# CAN_Node.net
KiCad netlist of a schematic drawn in Altium Designer
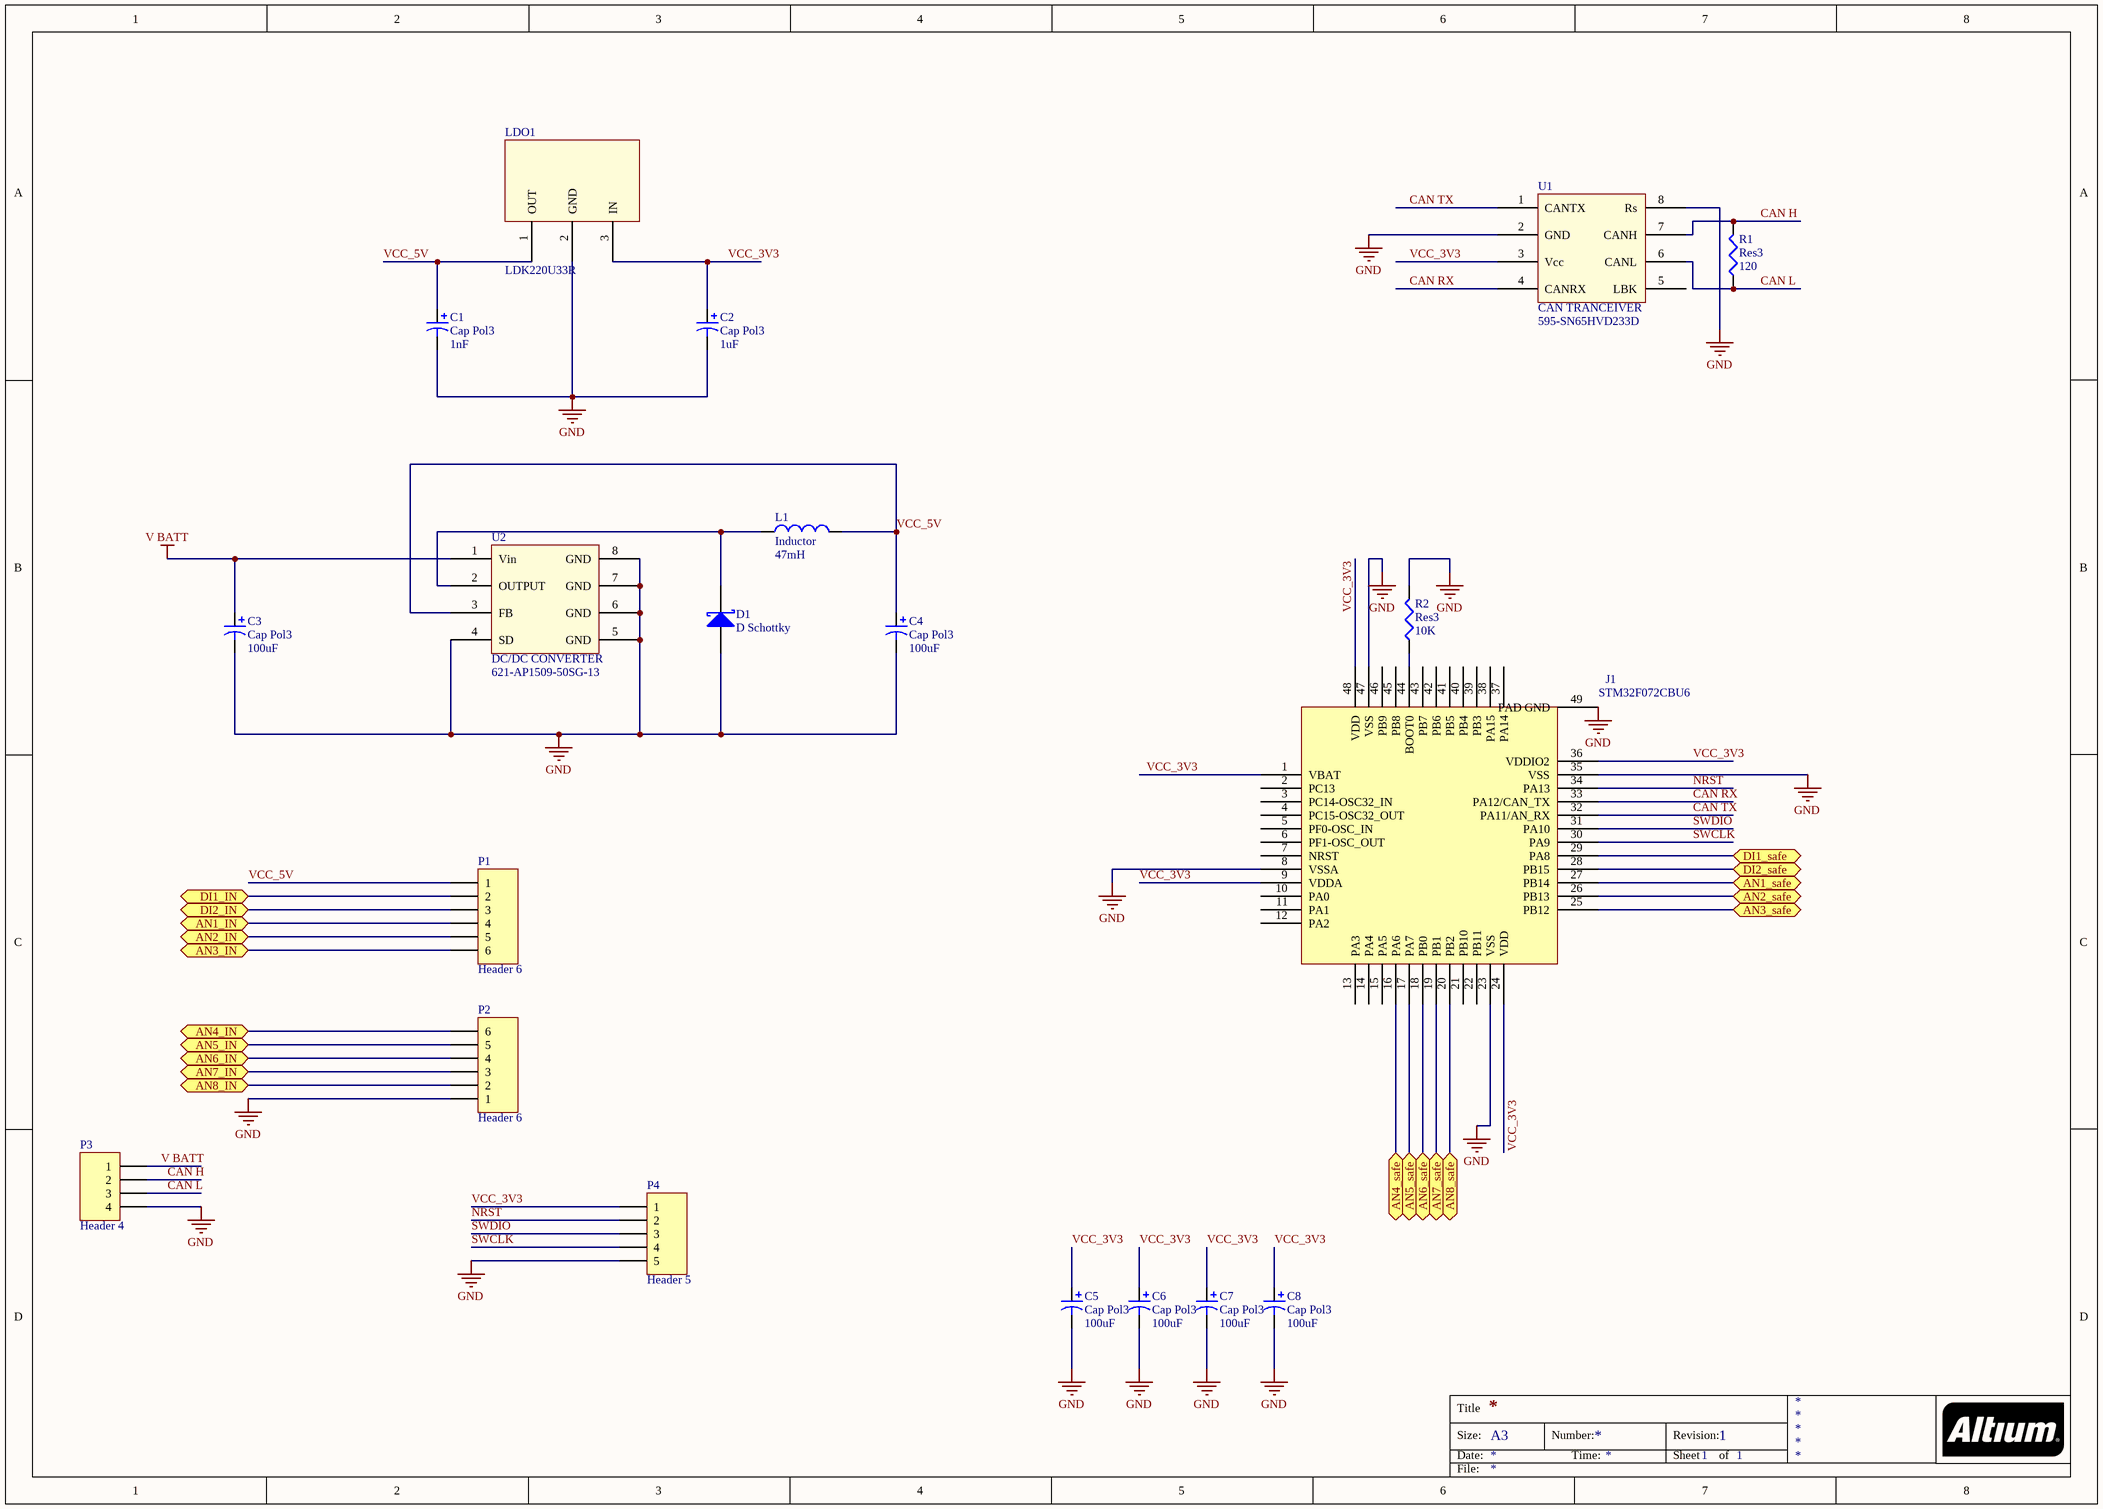
[diagram p0: CAN_Node.SchDoc]

(export (version "E")
  (design (tool "Eeschema 10.0.6"))
  (components
    (comp (ref "C1")
      (value "Cap Pol3")
      (footprint "C0805")
      (description "Polarized Capacitor (Surface Mount)")
      (fields (field (name "ALTIUM_VALUE") "1nF") (field (name "PUBLISHER") "Altium Limited"))
      (libsource (lib "Miscellaneous Devices") (part "Cap Pol3"))
    )
    (comp (ref "C2")
      (value "Cap Pol3")
      (footprint "C0805")
      (description "Polarized Capacitor (Surface Mount)")
      (fields (field (name "ALTIUM_VALUE") "1uF") (field (name "PUBLISHER") "Altium Limited"))
      (libsource (lib "Miscellaneous Devices") (part "Cap Pol3"))
    )
    (comp (ref "C3")
      (value "Cap Pol3")
      (footprint "C0805")
      (description "Polarized Capacitor (Surface Mount)")
      (fields (field (name "ALTIUM_VALUE") "100uF") (field (name "PUBLISHER") "Altium Limited"))
      (libsource (lib "Miscellaneous Devices") (part "Cap Pol3"))
    )
    (comp (ref "C4")
      (value "Cap Pol3")
      (footprint "C0805")
      (description "Polarized Capacitor (Surface Mount)")
      (fields (field (name "ALTIUM_VALUE") "100uF") (field (name "PUBLISHER") "Altium Limited"))
      (libsource (lib "Miscellaneous Devices") (part "Cap Pol3"))
    )
    (comp (ref "C5")
      (value "Cap Pol3")
      (footprint "C0805")
      (description "Polarized Capacitor (Surface Mount)")
      (fields (field (name "ALTIUM_VALUE") "100uF") (field (name "PUBLISHER") "Altium Limited"))
      (libsource (lib "Miscellaneous Devices") (part "Cap Pol3"))
    )
    (comp (ref "C6")
      (value "Cap Pol3")
      (footprint "C0805")
      (description "Polarized Capacitor (Surface Mount)")
      (fields (field (name "ALTIUM_VALUE") "100uF") (field (name "PUBLISHER") "Altium Limited"))
      (libsource (lib "Miscellaneous Devices") (part "Cap Pol3"))
    )
    (comp (ref "C7")
      (value "Cap Pol3")
      (footprint "C0805")
      (description "Polarized Capacitor (Surface Mount)")
      (fields (field (name "ALTIUM_VALUE") "100uF") (field (name "PUBLISHER") "Altium Limited"))
      (libsource (lib "Miscellaneous Devices") (part "Cap Pol3"))
    )
    (comp (ref "C8")
      (value "Cap Pol3")
      (footprint "C0805")
      (description "Polarized Capacitor (Surface Mount)")
      (fields (field (name "ALTIUM_VALUE") "100uF") (field (name "PUBLISHER") "Altium Limited"))
      (libsource (lib "Miscellaneous Devices") (part "Cap Pol3"))
    )
    (comp (ref "D1")
      (value "D Schottky")
      (footprint "SMB")
      (description "Schottky Diode")
      (fields (field (name "PUBLISHER") "Altium Limited"))
      (libsource (lib "Miscellaneous Devices") (part "D Schottky"))
    )
    (comp (ref "J1")
      (value "STM32F072CBU6")
      (footprint "STM32F072CBU6")
      (description "MICROCONTROLLER")
      (libsource (lib "CAN_Node") (part "STM32F072CBU6"))
    )
    (comp (ref "L1")
      (value "Inductor")
      (footprint "0402-A")
      (fields (field (name "ALTIUM_VALUE") "47mH") (field (name "PUBLISHER") "Altium Limited"))
      (libsource (lib "Miscellaneous Devices") (part "Inductor"))
    )
    (comp (ref "LDO1")
      (value "LDK220U33R")
      (footprint "SOT89-157P409X160-3N")
      (description "3.3V LDO")
      (libsource (lib "CAN_Node") (part "LDK220U33R"))
    )
    (comp (ref "P1")
      (value "Header 6")
      (footprint "HDR1X6")
      (description "Header, 6-Pin")
      (fields (field (name "PUBLISHER") "Altium Limited"))
      (libsource (lib "") (part "Header 6_1"))
    )
    (comp (ref "P2")
      (value "Header 6")
      (footprint "HDR1X6")
      (description "Header, 6-Pin")
      (fields (field (name "PUBLISHER") "Altium Limited"))
      (libsource (lib "Miscellaneous Connectors") (part "Header 6"))
    )
    (comp (ref "P3")
      (value "Header 4")
      (footprint "HDR1X4")
      (description "Header, 4-Pin")
      (fields (field (name "PUBLISHER") "Altium Limited"))
      (libsource (lib "Miscellaneous Connectors") (part "Header 4"))
    )
    (comp (ref "P4")
      (value "Header 5")
      (footprint "HDR1X5")
      (description "Header, 5-Pin")
      (fields (field (name "PUBLISHER") "Altium Limited"))
      (libsource (lib "Miscellaneous Connectors") (part "Header 5"))
    )
    (comp (ref "R1")
      (value "Res3")
      (footprint "J1-0603")
      (description "Resistor")
      (fields (field (name "ALTIUM_VALUE") "120") (field (name "PUBLISHER") "Altium Limited"))
      (libsource (lib "Miscellaneous Devices") (part "Res3"))
    )
    (comp (ref "R2")
      (value "Res3")
      (footprint "J1-0603")
      (description "Resistor")
      (fields (field (name "ALTIUM_VALUE") "10K") (field (name "PUBLISHER") "Altium Limited"))
      (libsource (lib "Miscellaneous Devices") (part "Res3"))
    )
    (comp (ref "U1")
      (value "CAN TRANCEIVER")
      (footprint "SOP8")
      (fields (field (name "SUPPLIER PART NUMBER 1") "595-SN65HVD233D"))
      (libsource (lib "CAN_Node") (part "595-SN65HVD233"))
    )
    (comp (ref "U2")
      (value "DC/DC CONVERTER")
      (footprint "SOP8")
      (fields (field (name "SUPPLIER PART NUMBER 1") "621-AP1509-50SG-13"))
      (libsource (lib "CAN_Node") (part "AP1509-50SG-13"))
    )
  )
  (nets
    (net (code "1") (name "/AN1_IN") (class "Default")
      (node (ref "P1") (pin "4") (pinfunction "4_4") (pintype "passive"))
    )
    (net (code "2") (name "/AN1_safe") (class "Default")
      (node (ref "J1") (pin "27") (pinfunction "PB14_27") (pintype "passive"))
    )
    (net (code "3") (name "/AN2_IN") (class "Default")
      (node (ref "P1") (pin "5") (pinfunction "5_5") (pintype "passive"))
    )
    (net (code "4") (name "/AN2_safe") (class "Default")
      (node (ref "J1") (pin "26") (pinfunction "PB13_26") (pintype "passive"))
    )
    (net (code "5") (name "/AN3_IN") (class "Default")
      (node (ref "P1") (pin "6") (pinfunction "6_6") (pintype "passive"))
    )
    (net (code "6") (name "/AN3_safe") (class "Default")
      (node (ref "J1") (pin "25") (pinfunction "PB12_25") (pintype "passive"))
    )
    (net (code "7") (name "/AN4_IN") (class "Default")
      (node (ref "P2") (pin "6") (pinfunction "6_6") (pintype "passive"))
    )
    (net (code "8") (name "/AN4_safe") (class "Default")
      (node (ref "J1") (pin "16") (pinfunction "PA6_16") (pintype "passive"))
    )
    (net (code "9") (name "/AN5_IN") (class "Default")
      (node (ref "P2") (pin "5") (pinfunction "5_5") (pintype "passive"))
    )
    (net (code "10") (name "/AN5_safe") (class "Default")
      (node (ref "J1") (pin "17") (pinfunction "PA7_17") (pintype "passive"))
    )
    (net (code "11") (name "/AN6_IN") (class "Default")
      (node (ref "P2") (pin "4") (pinfunction "4_4") (pintype "passive"))
    )
    (net (code "12") (name "/AN6_safe") (class "Default")
      (node (ref "J1") (pin "18") (pinfunction "PB0_18") (pintype "passive"))
    )
    (net (code "13") (name "/AN7_IN") (class "Default")
      (node (ref "P2") (pin "3") (pinfunction "3_3") (pintype "passive"))
    )
    (net (code "14") (name "/AN7_safe") (class "Default")
      (node (ref "J1") (pin "19") (pinfunction "PB1_19") (pintype "passive"))
    )
    (net (code "15") (name "/AN8_IN") (class "Default")
      (node (ref "P2") (pin "2") (pinfunction "2_2") (pintype "passive"))
    )
    (net (code "16") (name "/AN8_safe") (class "Default")
      (node (ref "J1") (pin "20") (pinfunction "PB2_20") (pintype "passive"))
    )
    (net (code "17") (name "/CAN H") (class "Default")
      (node (ref "P3") (pin "2") (pinfunction "2_2") (pintype "passive"))
      (node (ref "R1") (pin "2") (pinfunction "2_2") (pintype "passive"))
      (node (ref "U1") (pin "7") (pinfunction "CANH_7") (pintype "passive"))
    )
    (net (code "18") (name "/CAN L") (class "Default")
      (node (ref "P3") (pin "3") (pinfunction "3_3") (pintype "passive"))
      (node (ref "R1") (pin "1") (pinfunction "1_1") (pintype "passive"))
      (node (ref "U1") (pin "6") (pinfunction "CANL_6") (pintype "passive"))
    )
    (net (code "19") (name "/CAN RX") (class "Default")
      (node (ref "J1") (pin "33") (pinfunction "PA12/CAN_TX_33") (pintype "passive"))
      (node (ref "U1") (pin "4") (pinfunction "CANRX_4") (pintype "passive"))
    )
    (net (code "20") (name "/CAN TX") (class "Default")
      (node (ref "J1") (pin "32") (pinfunction "PA11/AN_RX_32") (pintype "passive"))
      (node (ref "U1") (pin "1") (pinfunction "CANTX_1") (pintype "passive"))
    )
    (net (code "21") (name "/DI1_IN") (class "Default")
      (node (ref "P1") (pin "2") (pinfunction "2_2") (pintype "passive"))
    )
    (net (code "22") (name "/DI1_safe") (class "Default")
      (node (ref "J1") (pin "29") (pinfunction "PA8_29") (pintype "passive"))
    )
    (net (code "23") (name "/DI2_IN") (class "Default")
      (node (ref "P1") (pin "3") (pinfunction "3_3") (pintype "passive"))
    )
    (net (code "24") (name "/DI2_safe") (class "Default")
      (node (ref "J1") (pin "28") (pinfunction "PB15_28") (pintype "passive"))
    )
    (net (code "25") (name "/NRST") (class "Default")
      (node (ref "J1") (pin "34") (pinfunction "PA13_34") (pintype "passive"))
      (node (ref "P4") (pin "2") (pinfunction "2_2") (pintype "passive"))
    )
    (net (code "26") (name "/SWCLK") (class "Default")
      (node (ref "J1") (pin "30") (pinfunction "PA9_30") (pintype "passive"))
      (node (ref "P4") (pin "4") (pinfunction "4_4") (pintype "passive"))
    )
    (net (code "27") (name "/SWDIO") (class "Default")
      (node (ref "J1") (pin "31") (pinfunction "PA10_31") (pintype "passive"))
      (node (ref "P4") (pin "3") (pinfunction "3_3") (pintype "passive"))
    )
    (net (code "28") (name "/VCC_3V3") (class "Default")
      (node (ref "C2") (pin "1") (pinfunction "1_1") (pintype "passive"))
      (node (ref "C5") (pin "1") (pinfunction "1_1") (pintype "passive"))
      (node (ref "C6") (pin "1") (pinfunction "1_1") (pintype "passive"))
      (node (ref "C7") (pin "1") (pinfunction "1_1") (pintype "passive"))
      (node (ref "C8") (pin "1") (pinfunction "1_1") (pintype "passive"))
      (node (ref "J1") (pin "1") (pinfunction "VBAT_1") (pintype "passive"))
      (node (ref "J1") (pin "24") (pinfunction "VDD_24") (pintype "passive"))
      (node (ref "J1") (pin "36") (pinfunction "VDDIO2_36") (pintype "passive"))
      (node (ref "J1") (pin "48") (pinfunction "VDD_48") (pintype "passive"))
      (node (ref "J1") (pin "9") (pinfunction "VDDA_9") (pintype "passive"))
      (node (ref "LDO1") (pin "3") (pinfunction "IN_3") (pintype "passive"))
      (node (ref "P4") (pin "1") (pinfunction "1_1") (pintype "passive"))
      (node (ref "U1") (pin "3") (pinfunction "Vcc_3") (pintype "passive"))
    )
    (net (code "29") (name "/VCC_5V") (class "Default")
      (node (ref "C1") (pin "1") (pinfunction "1_1") (pintype "passive"))
      (node (ref "C4") (pin "1") (pinfunction "1_1") (pintype "passive"))
      (node (ref "L1") (pin "2") (pinfunction "2_2") (pintype "passive"))
      (node (ref "LDO1") (pin "1") (pinfunction "OUT_1") (pintype "passive"))
      (node (ref "P1") (pin "1") (pinfunction "1_1") (pintype "passive"))
      (node (ref "U2") (pin "3") (pinfunction "FB_3") (pintype "passive"))
    )
    (net (code "30") (name "GND") (class "Default")
      (node (ref "C1") (pin "2") (pinfunction "2_2") (pintype "passive"))
      (node (ref "C2") (pin "2") (pinfunction "2_2") (pintype "passive"))
      (node (ref "C3") (pin "2") (pinfunction "2_2") (pintype "passive"))
      (node (ref "C4") (pin "2") (pinfunction "2_2") (pintype "passive"))
      (node (ref "C5") (pin "2") (pinfunction "2_2") (pintype "passive"))
      (node (ref "C6") (pin "2") (pinfunction "2_2") (pintype "passive"))
      (node (ref "C7") (pin "2") (pinfunction "2_2") (pintype "passive"))
      (node (ref "C8") (pin "2") (pinfunction "2_2") (pintype "passive"))
      (node (ref "D1") (pin "1") (pinfunction "A_1") (pintype "passive"))
      (node (ref "J1") (pin "23") (pinfunction "VSS_23") (pintype "passive"))
      (node (ref "J1") (pin "35") (pinfunction "VSS_35") (pintype "passive"))
      (node (ref "J1") (pin "47") (pinfunction "VSS_47") (pintype "passive"))
      (node (ref "J1") (pin "49") (pinfunction "PAD_GND_49") (pintype "passive"))
      (node (ref "J1") (pin "8") (pinfunction "VSSA_8") (pintype "passive"))
      (node (ref "LDO1") (pin "2") (pinfunction "GND_2") (pintype "passive"))
      (node (ref "P2") (pin "1") (pinfunction "1_1") (pintype "passive"))
      (node (ref "P3") (pin "4") (pinfunction "4_4") (pintype "passive"))
      (node (ref "P4") (pin "5") (pinfunction "5_5") (pintype "passive"))
      (node (ref "R2") (pin "2") (pinfunction "2_2") (pintype "passive"))
      (node (ref "U1") (pin "2") (pinfunction "GND_2") (pintype "passive"))
      (node (ref "U1") (pin "8") (pinfunction "Rs_8") (pintype "passive"))
      (node (ref "U2") (pin "4") (pinfunction "SD_4") (pintype "passive"))
      (node (ref "U2") (pin "5") (pinfunction "GND_5") (pintype "passive"))
      (node (ref "U2") (pin "6") (pinfunction "GND_6") (pintype "passive"))
      (node (ref "U2") (pin "7") (pinfunction "GND_7") (pintype "passive"))
      (node (ref "U2") (pin "8") (pinfunction "GND_8") (pintype "passive"))
    )
    (net (code "31") (name "Net-(D1-K)") (class "Default")
      (node (ref "D1") (pin "2") (pinfunction "K_2") (pintype "passive"))
      (node (ref "L1") (pin "1") (pinfunction "1_1") (pintype "passive"))
      (node (ref "U2") (pin "2") (pinfunction "OUTPUT_2") (pintype "passive"))
    )
    (net (code "32") (name "Net-(J1-BOOT0)") (class "Default")
      (node (ref "J1") (pin "44") (pinfunction "BOOT0_44") (pintype "passive"))
      (node (ref "R2") (pin "1") (pinfunction "1_1") (pintype "passive"))
    )
    (net (code "33") (name "V BATT") (class "Default")
      (node (ref "C3") (pin "1") (pinfunction "1_1") (pintype "passive"))
      (node (ref "P3") (pin "1") (pinfunction "1_1") (pintype "passive"))
      (node (ref "U2") (pin "1") (pinfunction "Vin_1") (pintype "passive"))
    )
    (net (code "34") (name "unconnected-(J1-NRST-Pad7)") (class "Default")
      (node (ref "J1") (pin "7") (pinfunction "NRST_7") (pintype "passive"))
    )
    (net (code "35") (name "unconnected-(J1-PA0-Pad10)") (class "Default")
      (node (ref "J1") (pin "10") (pinfunction "PA0_10") (pintype "passive"))
    )
    (net (code "36") (name "unconnected-(J1-PA1-Pad11)") (class "Default")
      (node (ref "J1") (pin "11") (pinfunction "PA1_11") (pintype "passive"))
    )
    (net (code "37") (name "unconnected-(J1-PA2-Pad12)") (class "Default")
      (node (ref "J1") (pin "12") (pinfunction "PA2_12") (pintype "passive"))
    )
    (net (code "38") (name "unconnected-(J1-PA3-Pad13)") (class "Default")
      (node (ref "J1") (pin "13") (pinfunction "PA3_13") (pintype "passive"))
    )
    (net (code "39") (name "unconnected-(J1-PA4-Pad14)") (class "Default")
      (node (ref "J1") (pin "14") (pinfunction "PA4_14") (pintype "passive"))
    )
    (net (code "40") (name "unconnected-(J1-PA5-Pad15)") (class "Default")
      (node (ref "J1") (pin "15") (pinfunction "PA5_15") (pintype "passive"))
    )
    (net (code "41") (name "unconnected-(J1-PA14-Pad37)") (class "Default")
      (node (ref "J1") (pin "37") (pinfunction "PA14_37") (pintype "passive"))
    )
    (net (code "42") (name "unconnected-(J1-PA15-Pad38)") (class "Default")
      (node (ref "J1") (pin "38") (pinfunction "PA15_38") (pintype "passive"))
    )
    (net (code "43") (name "unconnected-(J1-PB3-Pad39)") (class "Default")
      (node (ref "J1") (pin "39") (pinfunction "PB3_39") (pintype "passive"))
    )
    (net (code "44") (name "unconnected-(J1-PB4-Pad40)") (class "Default")
      (node (ref "J1") (pin "40") (pinfunction "PB4_40") (pintype "passive"))
    )
    (net (code "45") (name "unconnected-(J1-PB5-Pad41)") (class "Default")
      (node (ref "J1") (pin "41") (pinfunction "PB5_41") (pintype "passive"))
    )
    (net (code "46") (name "unconnected-(J1-PB6-Pad42)") (class "Default")
      (node (ref "J1") (pin "42") (pinfunction "PB6_42") (pintype "passive"))
    )
    (net (code "47") (name "unconnected-(J1-PB7-Pad43)") (class "Default")
      (node (ref "J1") (pin "43") (pinfunction "PB7_43") (pintype "passive"))
    )
    (net (code "48") (name "unconnected-(J1-PB8-Pad45)") (class "Default")
      (node (ref "J1") (pin "45") (pinfunction "PB8_45") (pintype "passive"))
    )
    (net (code "49") (name "unconnected-(J1-PB9-Pad46)") (class "Default")
      (node (ref "J1") (pin "46") (pinfunction "PB9_46") (pintype "passive"))
    )
    (net (code "50") (name "unconnected-(J1-PB10-Pad21)") (class "Default")
      (node (ref "J1") (pin "21") (pinfunction "PB10_21") (pintype "passive"))
    )
    (net (code "51") (name "unconnected-(J1-PB11-Pad22)") (class "Default")
      (node (ref "J1") (pin "22") (pinfunction "PB11_22") (pintype "passive"))
    )
    (net (code "52") (name "unconnected-(J1-PC13-Pad2)") (class "Default")
      (node (ref "J1") (pin "2") (pinfunction "PC13_2") (pintype "passive"))
    )
    (net (code "53") (name "unconnected-(J1-PC14-OSC32_IN-Pad3)") (class "Default")
      (node (ref "J1") (pin "3") (pinfunction "PC14-OSC32_IN_3") (pintype "passive"))
    )
    (net (code "54") (name "unconnected-(J1-PC15-OSC32_OUT-Pad4)") (class "Default")
      (node (ref "J1") (pin "4") (pinfunction "PC15-OSC32_OUT_4") (pintype "passive"))
    )
    (net (code "55") (name "unconnected-(J1-PF0-OSC_IN-Pad5)") (class "Default")
      (node (ref "J1") (pin "5") (pinfunction "PF0-OSC_IN_5") (pintype "passive"))
    )
    (net (code "56") (name "unconnected-(J1-PF1-OSC_OUT-Pad6)") (class "Default")
      (node (ref "J1") (pin "6") (pinfunction "PF1-OSC_OUT_6") (pintype "passive"))
    )
    (net (code "57") (name "unconnected-(U1-LBK-Pad5)") (class "Default")
      (node (ref "U1") (pin "5") (pinfunction "LBK_5") (pintype "passive"))
    )
  )
)
